# SCH_Hand_Watch_2026-02-17.net
KiCad netlist of a schematic drawn in EasyEDA
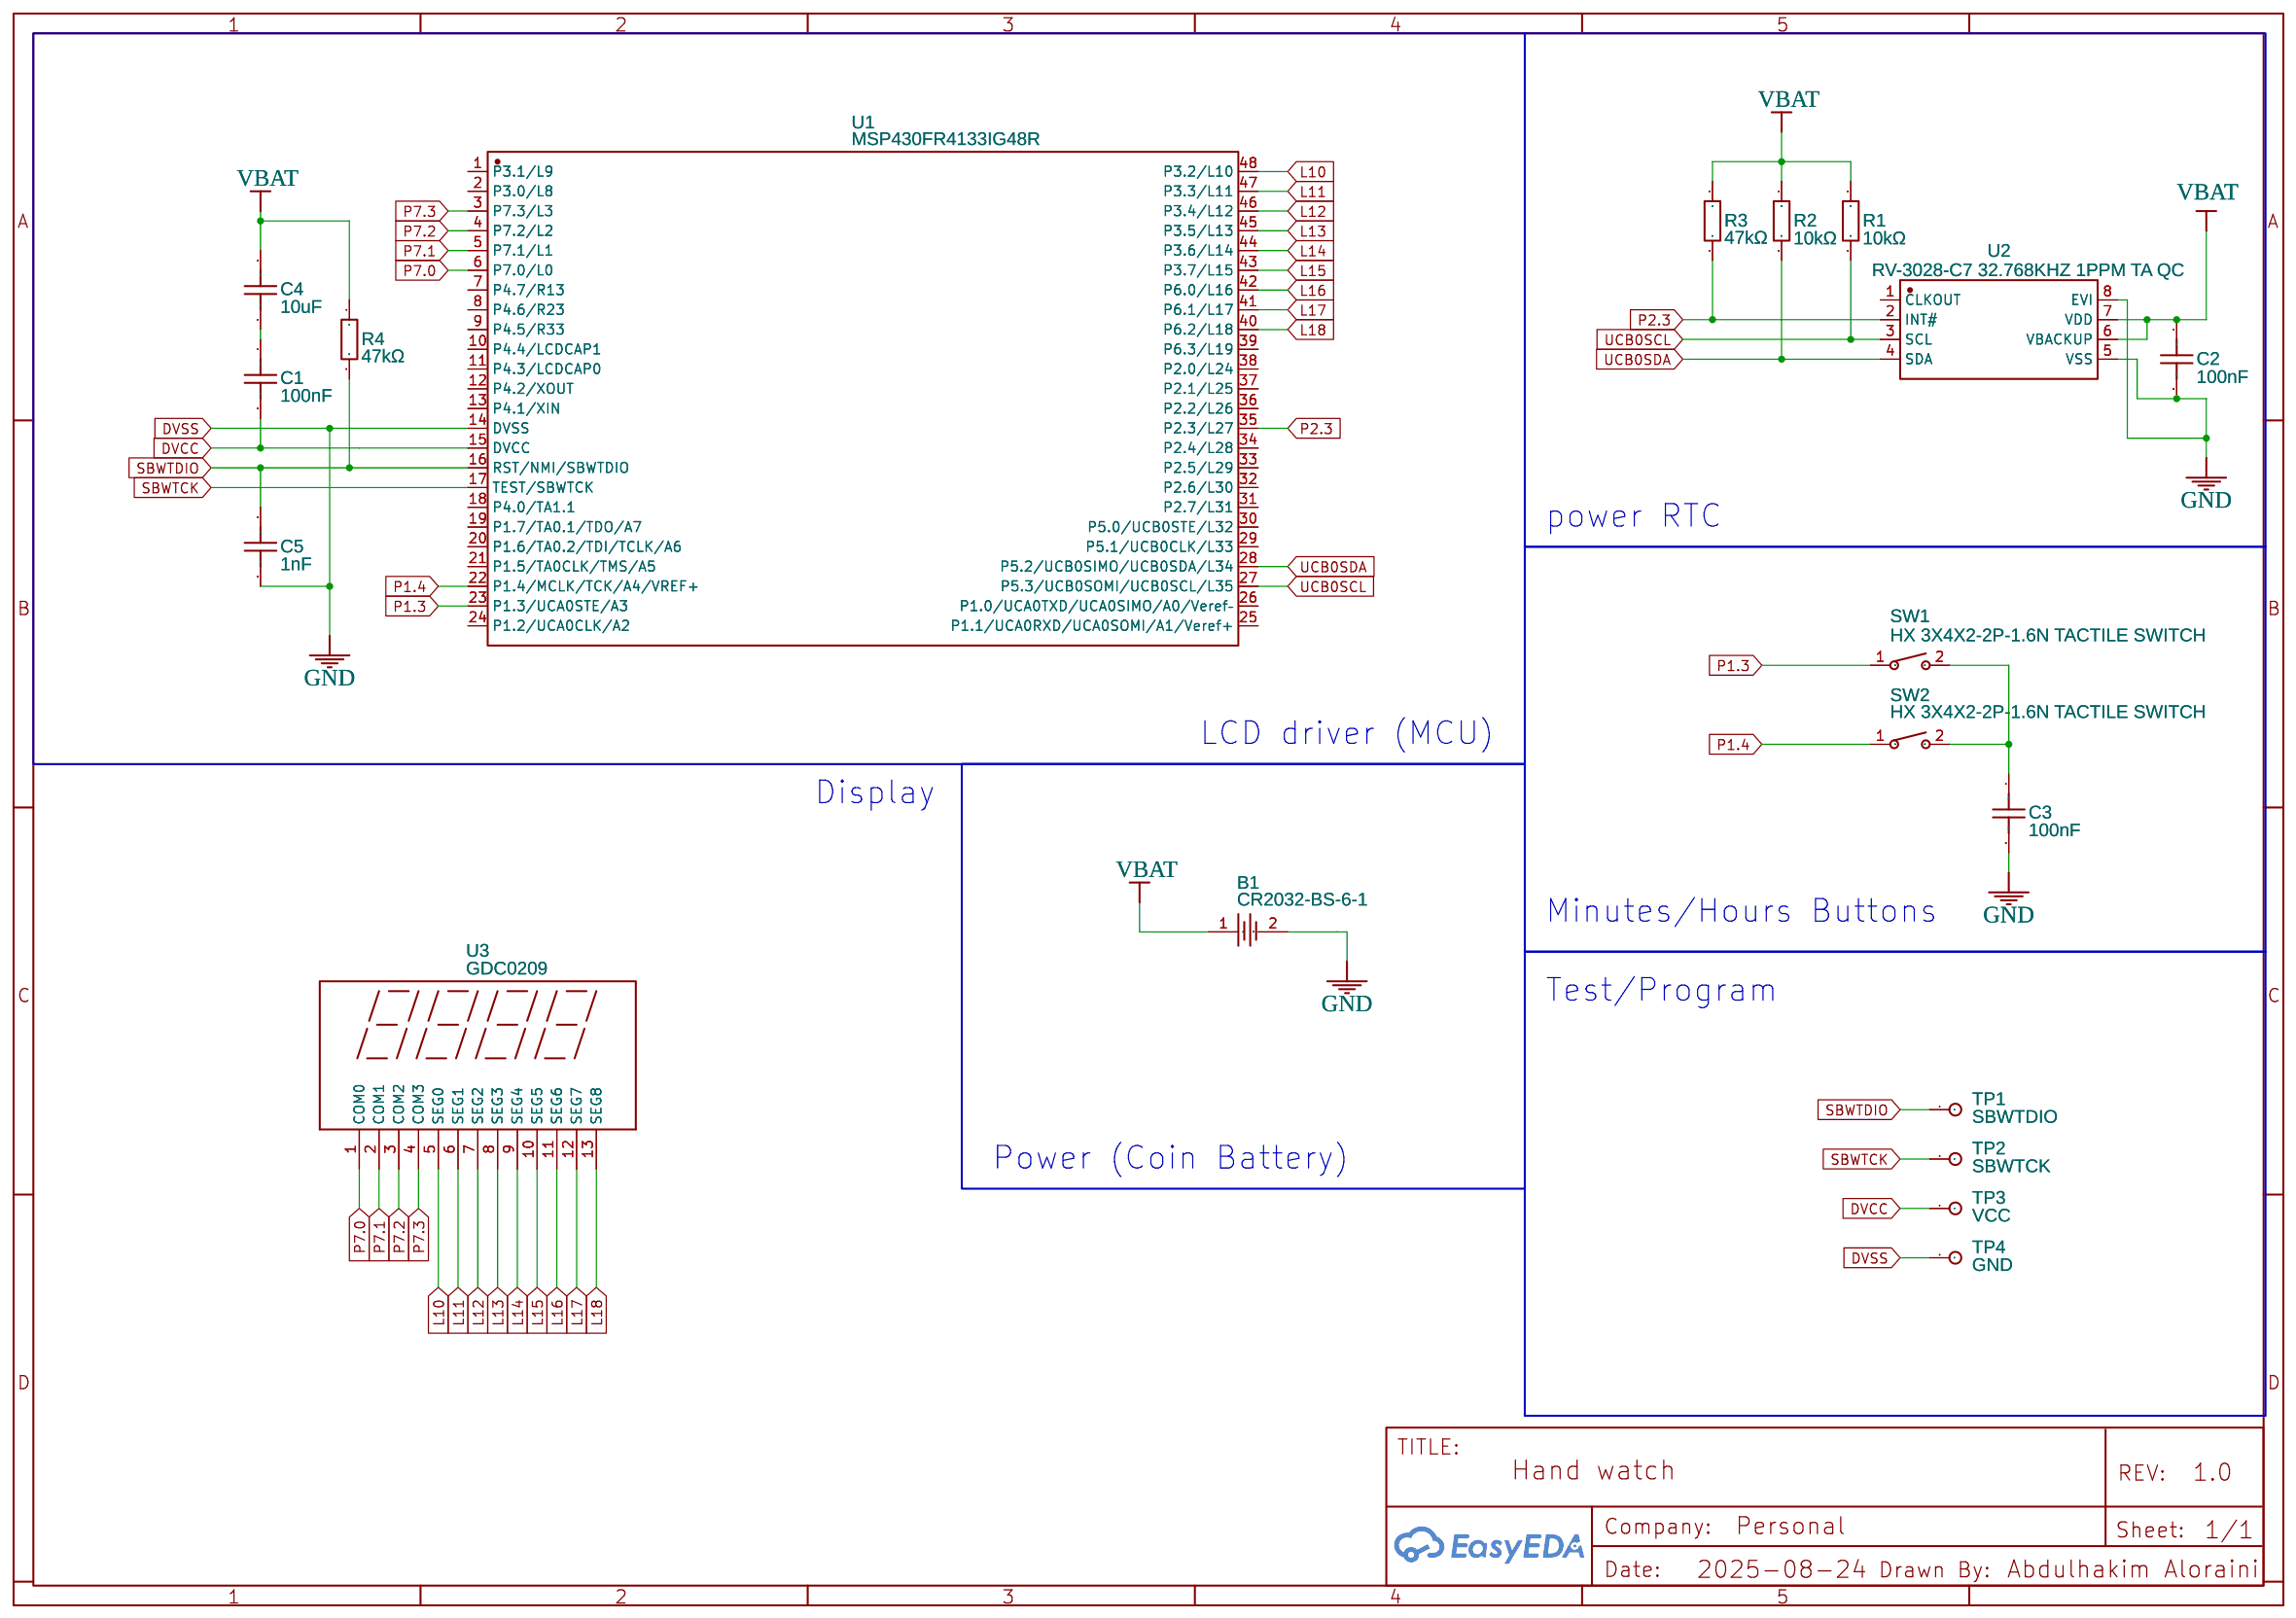
[diagram p0: schematic sheet]

(export (version "E")
  (design (tool "Eeschema 10.0.6"))
  (components
    (comp (ref "B1")
      (value "CR2032-BS-6-1")
      (fields (field (name "Manufacturer") "Q&J"))
      (libsource (lib "") (part "CR2032-BS-6-1"))
    )
    (comp (ref "C1")
      (value "100nF")
      (fields
        (field (name "Manufacturer Part") "CC0603KRX7R9BB104")
        (field (name "Manufacturer") "YAGEO(国巨)")
      )
      (libsource (lib "") (part "CC0603KRX7R9BB104"))
    )
    (comp (ref "C2")
      (value "100nF")
      (fields
        (field (name "Manufacturer Part") "CC0603KRX7R9BB104")
        (field (name "Manufacturer") "YAGEO(国巨)")
      )
      (libsource (lib "") (part "CC0603KRX7R9BB104"))
    )
    (comp (ref "C3")
      (value "100nF")
      (fields
        (field (name "Manufacturer Part") "CC0603KRX7R9BB104")
        (field (name "Manufacturer") "YAGEO(国巨)")
      )
      (libsource (lib "") (part "CC0603KRX7R9BB104"))
    )
    (comp (ref "C4")
      (value "10uF")
      (fields
        (field (name "Manufacturer Part") "TCC0805X5R106M160FTN")
        (field (name "Manufacturer") "CCTC(三环)")
      )
      (libsource (lib "") (part "TCC0805X5R106M160FTN"))
    )
    (comp (ref "C5")
      (value "1nF")
      (fields (field (name "Manufacturer Part") "04025C102KAT2A") (field (name "Manufacturer") "KYOCERA AVX"))
      (libsource (lib "") (part "04025C102KAT2A"))
    )
    (comp (ref "R1")
      (value "10kΩ")
      (fields
        (field (name "Manufacturer Part") "0603WAF1002T5E")
        (field (name "Manufacturer") "UNI-ROYAL(厚声)")
      )
      (libsource (lib "") (part "0603WAF1002T5E"))
    )
    (comp (ref "R2")
      (value "10kΩ")
      (fields
        (field (name "Manufacturer Part") "0603WAF1002T5E")
        (field (name "Manufacturer") "UNI-ROYAL(厚声)")
      )
      (libsource (lib "") (part "0603WAF1002T5E"))
    )
    (comp (ref "R3")
      (value "47kΩ")
      (fields (field (name "Manufacturer Part") "RMC060347K5%N") (field (name "Manufacturer") "Tyohm(幸亚电阻)"))
      (libsource (lib "") (part "RMC060347K5%N"))
    )
    (comp (ref "R4")
      (value "47kΩ")
      (fields (field (name "Manufacturer Part") "RMC060347K5%N") (field (name "Manufacturer") "Tyohm(幸亚电阻)"))
      (libsource (lib "") (part "RMC060347K5%N"))
    )
    (comp (ref "SW1")
      (value "HX 3X4X2-2P-1.6N TACTILE SWITCH")
      (fields
        (field (name "Manufacturer Part") "HX 3x4x2-2P-1.6N TACTILE SWITCH")
        (field (name "Manufacturer") "hanxia(韩下)")
      )
      (libsource (lib "") (part "HX 3X4X2-2P-1.6N TACTILE SWITCH"))
    )
    (comp (ref "SW2")
      (value "HX 3X4X2-2P-1.6N TACTILE SWITCH")
      (fields
        (field (name "Manufacturer Part") "HX 3x4x2-2P-1.6N TACTILE SWITCH")
        (field (name "Manufacturer") "hanxia(韩下)")
      )
      (libsource (lib "") (part "HX 3X4X2-2P-1.6N TACTILE SWITCH"))
    )
    (comp (ref "TP1") (value "SBWTDIO") (libsource (lib "") (part "CONNECTOR_TESTPOINT_2*2MM")))
    (comp (ref "TP2") (value "SBWTCK") (libsource (lib "") (part "CONNECTOR_TESTPOINT_2*2MM")))
    (comp (ref "TP3") (value "VCC") (libsource (lib "") (part "CONNECTOR_TESTPOINT_2*2MM")))
    (comp (ref "TP4") (value "GND") (libsource (lib "") (part "CONNECTOR_TESTPOINT_2*2MM")))
    (comp (ref "U1")
      (value "MSP430FR4133IG48R")
      (fields (field (name "Manufacturer") "TI(德州仪器)"))
      (libsource (lib "") (part "MSP430FR4133IG48R"))
    )
    (comp (ref "U2")
      (value "RV-3028-C7 32.768KHZ 1PPM TA QC")
      (fields
        (field (name "Manufacturer Part") "RV-3028-C7 32.768kHz 1ppm TA QC")
        (field (name "Manufacturer") "Micro Crystal(瑞士微晶)")
      )
      (libsource (lib "") (part "RV-3028-C7 32.768KHZ 1PPM TA QC"))
    )
    (comp (ref "U3")
      (value "GDC0209")
      (fields (field (name "Manufacturer") "DALIAN GOOD DISPLAY CO., LTD."))
      (libsource (lib "") (part "GDC0209"))
    )
  )
  (nets
    (net (code "1") (name "DVCC") (class "Default")
      (node (ref "C1") (pin "2") (pinfunction "2_2") (pintype "unspecified"))
      (node (ref "TP3") (pin "1") (pinfunction "1_1") (pintype "unspecified"))
      (node (ref "U1") (pin "15") (pinfunction "DVCC_15") (pintype "unspecified"))
    )
    (net (code "2") (name "DVSS") (class "Default")
      (node (ref "B1") (pin "2") (pinfunction "2_2") (pintype "input"))
      (node (ref "C2") (pin "2") (pinfunction "2_2") (pintype "unspecified"))
      (node (ref "C3") (pin "2") (pinfunction "2_2") (pintype "unspecified"))
      (node (ref "C5") (pin "2") (pinfunction "2_2") (pintype "unspecified"))
      (node (ref "TP4") (pin "1") (pinfunction "1_1") (pintype "unspecified"))
      (node (ref "U1") (pin "14") (pinfunction "DVSS_14") (pintype "unspecified"))
      (node (ref "U2") (pin "5") (pinfunction "VSS_5") (pintype "unspecified"))
      (node (ref "U2") (pin "8") (pinfunction "EVI_8") (pintype "unspecified"))
    )
    (net (code "3") (name "L10") (class "Default")
      (node (ref "U1") (pin "48") (pinfunction "P3.2/L10_48") (pintype "unspecified"))
      (node (ref "U3") (pin "5") (pinfunction "SEG0_5") (pintype "unspecified"))
    )
    (net (code "4") (name "L11") (class "Default")
      (node (ref "U1") (pin "47") (pinfunction "P3.3/L11_47") (pintype "unspecified"))
      (node (ref "U3") (pin "6") (pinfunction "SEG1_6") (pintype "unspecified"))
    )
    (net (code "5") (name "L12") (class "Default")
      (node (ref "U1") (pin "46") (pinfunction "P3.4/L12_46") (pintype "unspecified"))
      (node (ref "U3") (pin "7") (pinfunction "SEG2_7") (pintype "unspecified"))
    )
    (net (code "6") (name "L13") (class "Default")
      (node (ref "U1") (pin "45") (pinfunction "P3.5/L13_45") (pintype "unspecified"))
      (node (ref "U3") (pin "8") (pinfunction "SEG3_8") (pintype "unspecified"))
    )
    (net (code "7") (name "L14") (class "Default")
      (node (ref "U1") (pin "44") (pinfunction "P3.6/L14_44") (pintype "unspecified"))
      (node (ref "U3") (pin "9") (pinfunction "SEG4_9") (pintype "unspecified"))
    )
    (net (code "8") (name "L15") (class "Default")
      (node (ref "U1") (pin "43") (pinfunction "P3.7/L15_43") (pintype "unspecified"))
      (node (ref "U3") (pin "10") (pinfunction "SEG5_10") (pintype "unspecified"))
    )
    (net (code "9") (name "L16") (class "Default")
      (node (ref "U1") (pin "42") (pinfunction "P6.0/L16_42") (pintype "unspecified"))
      (node (ref "U3") (pin "11") (pinfunction "SEG6_11") (pintype "unspecified"))
    )
    (net (code "10") (name "L17") (class "Default")
      (node (ref "U1") (pin "41") (pinfunction "P6.1/L17_41") (pintype "unspecified"))
      (node (ref "U3") (pin "12") (pinfunction "SEG7_12") (pintype "unspecified"))
    )
    (net (code "11") (name "L18") (class "Default")
      (node (ref "U1") (pin "40") (pinfunction "P6.2/L18_40") (pintype "unspecified"))
      (node (ref "U3") (pin "13") (pinfunction "SEG8_13") (pintype "unspecified"))
    )
    (net (code "12") (name "Net-(C1-Pad1)") (class "Default")
      (node (ref "C1") (pin "1") (pinfunction "1_1") (pintype "unspecified"))
      (node (ref "C4") (pin "1") (pinfunction "1_1") (pintype "unspecified"))
    )
    (net (code "13") (name "Net-(C3-Pad1)") (class "Default")
      (node (ref "C3") (pin "1") (pinfunction "1_1") (pintype "unspecified"))
      (node (ref "SW1") (pin "2") (pinfunction "2_2") (pintype "unspecified"))
      (node (ref "SW2") (pin "2") (pinfunction "2_2") (pintype "unspecified"))
    )
    (net (code "14") (name "P1.3") (class "Default")
      (node (ref "SW1") (pin "1") (pinfunction "1_1") (pintype "unspecified"))
      (node (ref "U1") (pin "23") (pinfunction "P1.3/UCA0STE/A3_23") (pintype "unspecified"))
    )
    (net (code "15") (name "P1.4") (class "Default")
      (node (ref "SW2") (pin "1") (pinfunction "1_1") (pintype "unspecified"))
      (node (ref "U1") (pin "22") (pinfunction "P1.4/MCLK/TCK/A4/VREF+_22") (pintype "unspecified"))
    )
    (net (code "16") (name "P2.3") (class "Default")
      (node (ref "R3") (pin "2") (pinfunction "2_2") (pintype "unspecified"))
      (node (ref "U1") (pin "35") (pinfunction "P2.3/L27_35") (pintype "unspecified"))
      (node (ref "U2") (pin "2") (pinfunction "INT#_2") (pintype "unspecified"))
    )
    (net (code "17") (name "P7.0") (class "Default")
      (node (ref "U1") (pin "6") (pinfunction "P7.0/L0_6") (pintype "unspecified"))
      (node (ref "U3") (pin "1") (pinfunction "COM0_1") (pintype "unspecified"))
    )
    (net (code "18") (name "P7.1") (class "Default")
      (node (ref "U1") (pin "5") (pinfunction "P7.1/L1_5") (pintype "unspecified"))
      (node (ref "U3") (pin "2") (pinfunction "COM1_2") (pintype "unspecified"))
    )
    (net (code "19") (name "P7.2") (class "Default")
      (node (ref "U1") (pin "4") (pinfunction "P7.2/L2_4") (pintype "unspecified"))
      (node (ref "U3") (pin "3") (pinfunction "COM2_3") (pintype "unspecified"))
    )
    (net (code "20") (name "P7.3") (class "Default")
      (node (ref "U1") (pin "3") (pinfunction "P7.3/L3_3") (pintype "unspecified"))
      (node (ref "U3") (pin "4") (pinfunction "COM3_4") (pintype "unspecified"))
    )
    (net (code "21") (name "SBWTCK") (class "Default")
      (node (ref "TP2") (pin "1") (pinfunction "1_1") (pintype "unspecified"))
      (node (ref "U1") (pin "17") (pinfunction "TEST/SBWTCK_17") (pintype "unspecified"))
    )
    (net (code "22") (name "SBWTDIO") (class "Default")
      (node (ref "C5") (pin "1") (pinfunction "1_1") (pintype "unspecified"))
      (node (ref "R4") (pin "2") (pinfunction "2_2") (pintype "unspecified"))
      (node (ref "TP1") (pin "1") (pinfunction "1_1") (pintype "unspecified"))
      (node (ref "U1") (pin "16") (pinfunction "RST/NMI/SBWTDIO_16") (pintype "unspecified"))
    )
    (net (code "23") (name "UCB0SCL") (class "Default")
      (node (ref "R1") (pin "2") (pinfunction "2_2") (pintype "input"))
      (node (ref "U1") (pin "27") (pinfunction "P5.3/UCB0SOMI/UCB0SCL/L35_27") (pintype "unspecified"))
      (node (ref "U2") (pin "3") (pinfunction "SCL_3") (pintype "unspecified"))
    )
    (net (code "24") (name "UCB0SDA") (class "Default")
      (node (ref "R2") (pin "2") (pinfunction "2_2") (pintype "input"))
      (node (ref "U1") (pin "28") (pinfunction "P5.2/UCB0SIMO/UCB0SDA/L34_28") (pintype "unspecified"))
      (node (ref "U2") (pin "4") (pinfunction "SDA_4") (pintype "unspecified"))
    )
    (net (code "25") (name "VBAT") (class "Default")
      (node (ref "B1") (pin "1") (pinfunction "1_1") (pintype "input"))
      (node (ref "C2") (pin "1") (pinfunction "1_1") (pintype "unspecified"))
      (node (ref "C4") (pin "2") (pinfunction "2_2") (pintype "unspecified"))
      (node (ref "R1") (pin "1") (pinfunction "1_1") (pintype "input"))
      (node (ref "R2") (pin "1") (pinfunction "1_1") (pintype "input"))
      (node (ref "R3") (pin "1") (pinfunction "1_1") (pintype "unspecified"))
      (node (ref "R4") (pin "1") (pinfunction "1_1") (pintype "unspecified"))
      (node (ref "U2") (pin "6") (pinfunction "VBACKUP_6") (pintype "unspecified"))
      (node (ref "U2") (pin "7") (pinfunction "VDD_7") (pintype "unspecified"))
    )
    (net (code "26") (name "unconnected-(U1-P1.0{slash}UCA0TXD{slash}UCA0SIMO{slash}A0{slash}Veref–-Pad26)") (class "Default")
      (node (ref "U1") (pin "26") (pinfunction "P1.0/UCA0TXD/UCA0SIMO/A0/Veref–_26") (pintype "unspecified"))
    )
    (net (code "27") (name "unconnected-(U1-P1.1{slash}UCA0RXD{slash}UCA0SOMI{slash}A1{slash}Veref+-Pad25)") (class "Default")
      (node (ref "U1") (pin "25") (pinfunction "P1.1/UCA0RXD/UCA0SOMI/A1/Veref+_25") (pintype "unspecified"))
    )
    (net (code "28") (name "unconnected-(U1-P1.2{slash}UCA0CLK{slash}A2-Pad24)") (class "Default")
      (node (ref "U1") (pin "24") (pinfunction "P1.2/UCA0CLK/A2_24") (pintype "unspecified"))
    )
    (net (code "29") (name "unconnected-(U1-P1.5{slash}TA0CLK{slash}TMS{slash}A5-Pad21)") (class "Default")
      (node (ref "U1") (pin "21") (pinfunction "P1.5/TA0CLK/TMS/A5_21") (pintype "unspecified"))
    )
    (net (code "30") (name "unconnected-(U1-P1.6{slash}TA0.2{slash}TDI{slash}TCLK{slash}A6-Pad20)") (class "Default")
      (node (ref "U1") (pin "20") (pinfunction "P1.6/TA0.2/TDI/TCLK/A6_20") (pintype "unspecified"))
    )
    (net (code "31") (name "unconnected-(U1-P1.7{slash}TA0.1{slash}TDO{slash}A7-Pad19)") (class "Default")
      (node (ref "U1") (pin "19") (pinfunction "P1.7/TA0.1/TDO/A7_19") (pintype "unspecified"))
    )
    (net (code "32") (name "unconnected-(U1-P2.0{slash}L24-Pad38)") (class "Default")
      (node (ref "U1") (pin "38") (pinfunction "P2.0/L24_38") (pintype "unspecified"))
    )
    (net (code "33") (name "unconnected-(U1-P2.1{slash}L25-Pad37)") (class "Default")
      (node (ref "U1") (pin "37") (pinfunction "P2.1/L25_37") (pintype "unspecified"))
    )
    (net (code "34") (name "unconnected-(U1-P2.2{slash}L26-Pad36)") (class "Default")
      (node (ref "U1") (pin "36") (pinfunction "P2.2/L26_36") (pintype "unspecified"))
    )
    (net (code "35") (name "unconnected-(U1-P2.4{slash}L28-Pad34)") (class "Default")
      (node (ref "U1") (pin "34") (pinfunction "P2.4/L28_34") (pintype "unspecified"))
    )
    (net (code "36") (name "unconnected-(U1-P2.5{slash}L29-Pad33)") (class "Default")
      (node (ref "U1") (pin "33") (pinfunction "P2.5/L29_33") (pintype "unspecified"))
    )
    (net (code "37") (name "unconnected-(U1-P2.6{slash}L30-Pad32)") (class "Default")
      (node (ref "U1") (pin "32") (pinfunction "P2.6/L30_32") (pintype "unspecified"))
    )
    (net (code "38") (name "unconnected-(U1-P2.7{slash}L31-Pad31)") (class "Default")
      (node (ref "U1") (pin "31") (pinfunction "P2.7/L31_31") (pintype "unspecified"))
    )
    (net (code "39") (name "unconnected-(U1-P3.0{slash}L8-Pad2)") (class "Default")
      (node (ref "U1") (pin "2") (pinfunction "P3.0/L8_2") (pintype "unspecified"))
    )
    (net (code "40") (name "unconnected-(U1-P3.1{slash}L9-Pad1)") (class "Default")
      (node (ref "U1") (pin "1") (pinfunction "P3.1/L9_1") (pintype "unspecified"))
    )
    (net (code "41") (name "unconnected-(U1-P4.0{slash}TA1.1-Pad18)") (class "Default")
      (node (ref "U1") (pin "18") (pinfunction "P4.0/TA1.1_18") (pintype "unspecified"))
    )
    (net (code "42") (name "unconnected-(U1-P4.1{slash}XIN-Pad13)") (class "Default")
      (node (ref "U1") (pin "13") (pinfunction "P4.1/XIN_13") (pintype "unspecified"))
    )
    (net (code "43") (name "unconnected-(U1-P4.2{slash}XOUT-Pad12)") (class "Default")
      (node (ref "U1") (pin "12") (pinfunction "P4.2/XOUT_12") (pintype "unspecified"))
    )
    (net (code "44") (name "unconnected-(U1-P4.3{slash}LCDCAP0-Pad11)") (class "Default")
      (node (ref "U1") (pin "11") (pinfunction "P4.3/LCDCAP0_11") (pintype "unspecified"))
    )
    (net (code "45") (name "unconnected-(U1-P4.4{slash}LCDCAP1-Pad10)") (class "Default")
      (node (ref "U1") (pin "10") (pinfunction "P4.4/LCDCAP1_10") (pintype "unspecified"))
    )
    (net (code "46") (name "unconnected-(U1-P4.5{slash}R33-Pad9)") (class "Default")
      (node (ref "U1") (pin "9") (pinfunction "P4.5/R33_9") (pintype "unspecified"))
    )
    (net (code "47") (name "unconnected-(U1-P4.6{slash}R23-Pad8)") (class "Default")
      (node (ref "U1") (pin "8") (pinfunction "P4.6/R23_8") (pintype "unspecified"))
    )
    (net (code "48") (name "unconnected-(U1-P4.7{slash}R13-Pad7)") (class "Default")
      (node (ref "U1") (pin "7") (pinfunction "P4.7/R13_7") (pintype "unspecified"))
    )
    (net (code "49") (name "unconnected-(U1-P5.0{slash}UCB0STE{slash}L32-Pad30)") (class "Default")
      (node (ref "U1") (pin "30") (pinfunction "P5.0/UCB0STE/L32_30") (pintype "unspecified"))
    )
    (net (code "50") (name "unconnected-(U1-P5.1{slash}UCB0CLK{slash}L33-Pad29)") (class "Default")
      (node (ref "U1") (pin "29") (pinfunction "P5.1/UCB0CLK/L33_29") (pintype "unspecified"))
    )
    (net (code "51") (name "unconnected-(U1-P6.3{slash}L19-Pad39)") (class "Default")
      (node (ref "U1") (pin "39") (pinfunction "P6.3/L19_39") (pintype "unspecified"))
    )
    (net (code "52") (name "unconnected-(U2-CLKOUT-Pad1)") (class "Default")
      (node (ref "U2") (pin "1") (pinfunction "CLKOUT_1") (pintype "unspecified"))
    )
  )
)
